# SolarWing.net
KiCad netlist of a schematic drawn in EAGLE
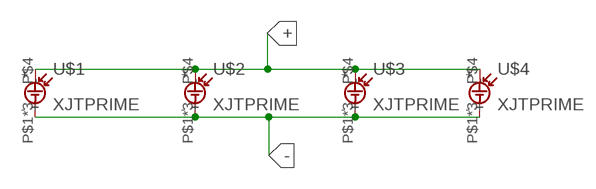
[diagram p0: schematic, sheet 1]

(export (version "E")
  (design (tool "Eeschema 10.0.6"))
  (components
    (comp (ref "U$1")
      (value "XJTPRIME")
      (footprint "eagle-import:XJTPRIME")
      (libsource (lib "eagle-import") (part "XJTPRIME"))
    )
    (comp (ref "U$2")
      (value "XJTPRIME")
      (footprint "eagle-import:XJTPRIME")
      (libsource (lib "eagle-import") (part "XJTPRIME"))
    )
    (comp (ref "U$3")
      (value "XJTPRIME")
      (footprint "eagle-import:XJTPRIME")
      (libsource (lib "eagle-import") (part "XJTPRIME"))
    )
    (comp (ref "U$4")
      (value "XJTPRIME")
      (footprint "eagle-import:XJTPRIME")
      (libsource (lib "eagle-import") (part "XJTPRIME"))
    )
  )
  (nets
    (net (code "1") (name "+") (class "Default")
      (node (ref "U$1") (pin "P$4") (pinfunction "+_P$4") (pintype "power_in"))
      (node (ref "U$2") (pin "P$4") (pinfunction "+_P$4") (pintype "power_in"))
      (node (ref "U$3") (pin "P$4") (pinfunction "+_P$4") (pintype "power_in"))
      (node (ref "U$4") (pin "P$4") (pinfunction "+_P$4") (pintype "power_in"))
    )
    (net (code "2") (name "-") (class "Default")
      (node (ref "U$1") (pin "P$1") (pinfunction "-_P$1") (pintype "power_in"))
      (node (ref "U$1") (pin "P$2") (pinfunction "-_P$2") (pintype "power_in"))
      (node (ref "U$1") (pin "P$3") (pinfunction "-_P$3") (pintype "power_in"))
      (node (ref "U$2") (pin "P$1") (pinfunction "-_P$1") (pintype "power_in"))
      (node (ref "U$2") (pin "P$2") (pinfunction "-_P$2") (pintype "power_in"))
      (node (ref "U$2") (pin "P$3") (pinfunction "-_P$3") (pintype "power_in"))
      (node (ref "U$3") (pin "P$1") (pinfunction "-_P$1") (pintype "power_in"))
      (node (ref "U$3") (pin "P$2") (pinfunction "-_P$2") (pintype "power_in"))
      (node (ref "U$3") (pin "P$3") (pinfunction "-_P$3") (pintype "power_in"))
      (node (ref "U$4") (pin "P$1") (pinfunction "-_P$1") (pintype "power_in"))
      (node (ref "U$4") (pin "P$2") (pinfunction "-_P$2") (pintype "power_in"))
      (node (ref "U$4") (pin "P$3") (pinfunction "-_P$3") (pintype "power_in"))
    )
  )
)
